# Sheet5.net
KiCad netlist of a schematic drawn in Altium Designer
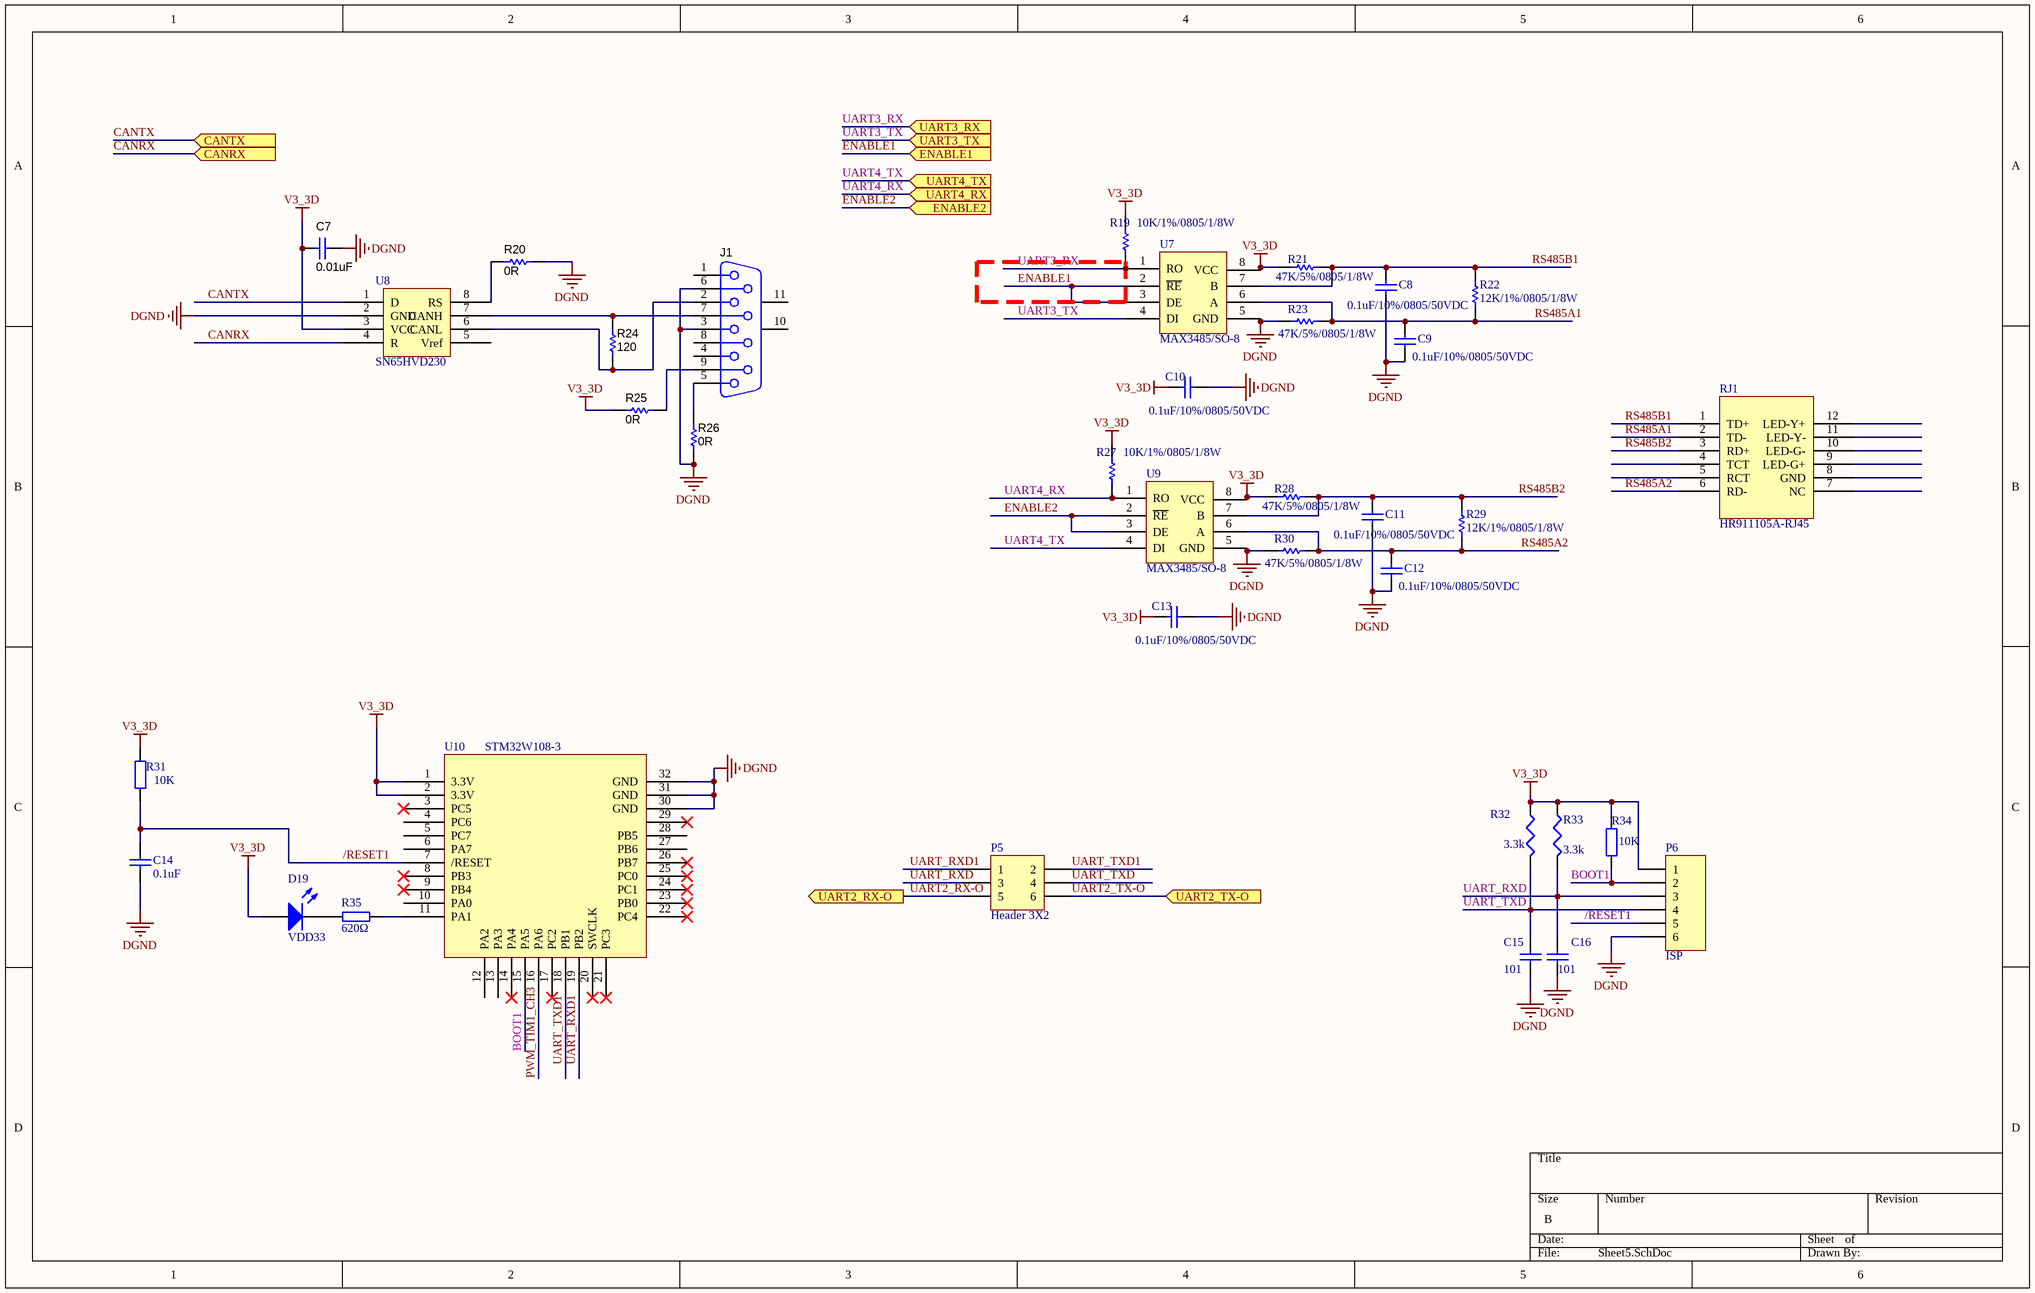
[diagram p0: Sheet5.SchDoc]

(export (version "E")
  (design (tool "Eeschema 10.0.6"))
  (components
    (comp (ref "C7")
      (value "~")
      (footprint "0805_cap")
      (description "CAP, CERM, 0.01uF, 16V, +/-10%, X7R, 0402")
      (fields
        (field (name "PARTNUMBER") "C1005X7R1C103K")
        (field (name "VALUEDISPLAYED") "0.01uF")
        (field (name "MANUFACTURER") "TDK")
        (field (name "PUBLISHER") "Texas Instruments")
      )
      (libsource (lib "Capacitor_Ceramic") (part "C1005X7R1C103K"))
    )
    (comp (ref "C8")
      (value "0.1uF/10%/0805/50VDC")
      (footprint "C-0805")
      (libsource (lib "浙江关西电机数据库") (part "CAP_Non-polarity"))
    )
    (comp (ref "C9")
      (value "0.1uF/10%/0805/50VDC")
      (footprint "C-0805")
      (libsource (lib "浙江关西电机数据库") (part "CAP_Non-polarity"))
    )
    (comp (ref "C10")
      (value "0.1uF/10%/0805/50VDC")
      (footprint "C-0805")
      (libsource (lib "浙江关西电机数据库") (part "CAP_Non-polarity"))
    )
    (comp (ref "C11")
      (value "0.1uF/10%/0805/50VDC")
      (footprint "C-0805")
      (libsource (lib "浙江关西电机数据库") (part "CAP_Non-polarity"))
    )
    (comp (ref "C12")
      (value "0.1uF/10%/0805/50VDC")
      (footprint "C-0805")
      (libsource (lib "浙江关西电机数据库") (part "CAP_Non-polarity"))
    )
    (comp (ref "C13")
      (value "0.1uF/10%/0805/50VDC")
      (footprint "C-0805")
      (libsource (lib "浙江关西电机数据库") (part "CAP_Non-polarity"))
    )
    (comp (ref "C14")
      (value "0.1uF")
      (footprint "C0805")
      (description "Capacitor")
      (fields (field (name "PUBLISHER") "Altium Limited"))
      (libsource (lib "Miscellaneous Devices") (part "Cap"))
    )
    (comp (ref "C15")
      (value "101")
      (footprint "C0805")
      (description "Capacitor")
      (fields (field (name "PUBLISHER") "Altium Limited"))
      (libsource (lib "Miscellaneous Devices") (part "Cap"))
    )
    (comp (ref "C16")
      (value "101")
      (footprint "C0805")
      (description "Capacitor")
      (fields (field (name "PUBLISHER") "Altium Limited"))
      (libsource (lib "Miscellaneous Devices") (part "Cap"))
    )
    (comp (ref "D19")
      (value "VDD33")
      (footprint "0805LED")
      (description "Typical BLUE SiC LED")
      (fields (field (name "PUBLISHER") "Altium Limited"))
      (libsource (lib "Miscellaneous Devices") (part "LED3"))
    )
    (comp (ref "J1")
      (value "~")
      (footprint "CONN_1734348-1")
      (description "Conn D-SUB RCPT R/A 9POS GOLD/FL, TH")
      (fields
        (field (name "PARTNUMBER") "1734348-1")
        (field (name "MANUFACTURER") "TE Connectivity")
        (field (name "SYMBOLCREATOR") "a0412235")
        (field (name "PUBLISHER") "Texas Instruments")
      )
      (libsource (lib "Connectors") (part "1734348-1"))
    )
    (comp (ref "P5")
      (value "Header 3X2")
      (footprint "HDR2X3")
      (description "Header, 3-Pin, Dual row")
      (fields (field (name "PUBLISHER") "Altium Limited"))
      (libsource (lib "Miscellaneous Connectors") (part "Header 3X2"))
    )
    (comp (ref "P6")
      (value "ISP")
      (footprint "SIP-6B")
      (description "Header, 6-Pin")
      (fields (field (name "PUBLISHER") "Altium Limited"))
      (libsource (lib "Miscellaneous Connectors") (part "Header 6"))
    )
    (comp (ref "R19")
      (value "10K/1%/0805/1/8W")
      (footprint "R-0805")
      (fields (field (name "PART NUMBER") "ASR-0028BA"))
      (libsource (lib "浙江关西电机数据库") (part "RES_1"))
    )
    (comp (ref "R20")
      (value "0R")
      (footprint "0805_HV")
      (description "RES, 0 ohm, 1%, 0.125W, 0805")
      (fields
        (field (name "PARTNUMBER") "CRCW080560R4FKEA")
        (field (name "MANUFACTURER") "Vishay-Dale")
        (field (name "PUBLISHER") "Texas Instruments")
      )
      (libsource (lib "Resistor_0805") (part "CRCW080560R4FKEA"))
    )
    (comp (ref "R21")
      (value "47K/5%/0805/1/8W")
      (footprint "R-0805")
      (fields (field (name "PART NUMBER") "ASR-0134BA"))
      (libsource (lib "浙江关西电机数据库") (part "RES_1"))
    )
    (comp (ref "R22")
      (value "12K/1%/0805/1/8W")
      (footprint "R-0805")
      (libsource (lib "浙江关西电机数据库") (part "RES_1"))
    )
    (comp (ref "R23")
      (value "47K/5%/0805/1/8W")
      (footprint "R-0805")
      (fields (field (name "PART NUMBER") "ASR-0134BA"))
      (libsource (lib "浙江关西电机数据库") (part "RES_1"))
    )
    (comp (ref "R24")
      (value "120")
      (footprint "0805_HV")
      (description "RES, 120ohm, 1%, 0.125W, 0805")
      (fields
        (field (name "PARTNUMBER") "CRCW080560R4FKEA")
        (field (name "MANUFACTURER") "Vishay-Dale")
        (field (name "PUBLISHER") "Texas Instruments")
      )
      (libsource (lib "Resistor_0805") (part "CRCW080560R4FKEA"))
    )
    (comp (ref "R25")
      (value "0R")
      (footprint "0805_HV")
      (description "RES, 0 ohm, 1%, 0.125W, 0805")
      (fields
        (field (name "PARTNUMBER") "CRCW080560R4FKEA")
        (field (name "MANUFACTURER") "Vishay-Dale")
        (field (name "PUBLISHER") "Texas Instruments")
      )
      (libsource (lib "Resistor_0805") (part "CRCW080560R4FKEA"))
    )
    (comp (ref "R26")
      (value "0R")
      (footprint "0805_HV")
      (description "RES, 0 ohm, 1%, 0.125W, 0805")
      (fields
        (field (name "PARTNUMBER") "CRCW080560R4FKEA")
        (field (name "MANUFACTURER") "Vishay-Dale")
        (field (name "PUBLISHER") "Texas Instruments")
      )
      (libsource (lib "Resistor_0805") (part "CRCW080560R4FKEA"))
    )
    (comp (ref "R27")
      (value "10K/1%/0805/1/8W")
      (footprint "R-0805")
      (fields (field (name "PART NUMBER") "ASR-0028BA"))
      (libsource (lib "浙江关西电机数据库") (part "RES_1"))
    )
    (comp (ref "R28")
      (value "47K/5%/0805/1/8W")
      (footprint "R-0805")
      (fields (field (name "PART NUMBER") "ASR-0134BA"))
      (libsource (lib "浙江关西电机数据库") (part "RES_1"))
    )
    (comp (ref "R29")
      (value "12K/1%/0805/1/8W")
      (footprint "R-0805")
      (libsource (lib "浙江关西电机数据库") (part "RES_1"))
    )
    (comp (ref "R30")
      (value "47K/5%/0805/1/8W")
      (footprint "R-0805")
      (fields (field (name "PART NUMBER") "ASR-0134BA"))
      (libsource (lib "浙江关西电机数据库") (part "RES_1"))
    )
    (comp (ref "R31")
      (value "10K")
      (footprint "0805")
      (description "Resistor")
      (fields (field (name "Comment") "Res2") (field (name "PUBLISHER") "Altium Limited"))
      (libsource (lib "Miscellaneous Devices") (part "Res2"))
    )
    (comp (ref "R32")
      (value "3.3k")
      (footprint "R0805")
      (description "Resistor")
      (fields (field (name "PUBLISHER") "Altium Limited"))
      (libsource (lib "Miscellaneous Devices") (part "Res3"))
    )
    (comp (ref "R33")
      (value "3.3k")
      (footprint "R0805")
      (description "Resistor")
      (fields (field (name "PUBLISHER") "Altium Limited"))
      (libsource (lib "Miscellaneous Devices") (part "Res3"))
    )
    (comp (ref "R34")
      (value "10K")
      (footprint "R0805")
      (description "Resistor")
      (fields (field (name "Comment") "Res2") (field (name "PUBLISHER") "Altium Limited"))
      (libsource (lib "Miscellaneous Devices") (part "Res2"))
    )
    (comp (ref "R35")
      (value "620Ω")
      (footprint "R0805")
      (description "R")
      (libsource (lib "Haze") (part "RES"))
    )
    (comp (ref "RJ1")
      (value "HR911105A-RJ45")
      (footprint "HR911105A")
      (libsource (lib "moonlight") (part "HR911105A-RJ45"))
    )
    (comp (ref "U7")
      (value "MAX3485/SO-8")
      (footprint "SO-G8")
      (libsource (lib "SCHLIBRARIES") (part "MAX485"))
    )
    (comp (ref "U8")
      (value "SN65HVD230")
      (footprint "SO-G8")
      (libsource (lib "SCHLIBRARIES") (part "SN65HVD230"))
    )
    (comp (ref "U9")
      (value "MAX3485/SO-8")
      (footprint "SO-G8")
      (libsource (lib "SCHLIBRARIES") (part "MAX485"))
    )
    (comp (ref "U10")
      (value "STM32W108-3")
      (footprint "STM32W108-3")
      (libsource (lib "STM32W108-3") (part "STM32W108-3"))
    )
  )
  (nets
    (net (code "1") (name "/BOOT1") (class "Default")
      (node (ref "P6") (pin "2") (pinfunction "2_2") (pintype "passive"))
      (node (ref "R34") (pin "1") (pinfunction "1_1") (pintype "passive"))
      (node (ref "U10") (pin "15") (pinfunction "PA5_15") (pintype "passive"))
    )
    (net (code "2") (name "/CANRX") (class "Default")
      (node (ref "U8") (pin "4") (pinfunction "R_4") (pintype "passive"))
    )
    (net (code "3") (name "/CANTX") (class "Default")
      (node (ref "U8") (pin "1") (pinfunction "D_1") (pintype "passive"))
    )
    (net (code "4") (name "/ENABLE1") (class "Default")
      (node (ref "U7") (pin "2") (pinfunction "~{RE}_2") (pintype "passive"))
      (node (ref "U7") (pin "3") (pinfunction "DE_3") (pintype "passive"))
    )
    (net (code "5") (name "/ENABLE2") (class "Default")
      (node (ref "U9") (pin "2") (pinfunction "~{RE}_2") (pintype "passive"))
      (node (ref "U9") (pin "3") (pinfunction "DE_3") (pintype "passive"))
    )
    (net (code "6") (name "/PWM_TIM1_CH3") (class "Default")
      (node (ref "U10") (pin "16") (pinfunction "PA6_16") (pintype "passive"))
    )
    (net (code "7") (name "/RS485A1") (class "Default")
      (node (ref "C9") (pin "2") (pinfunction "2_2") (pintype "passive"))
      (node (ref "R22") (pin "1") (pinfunction "1_1") (pintype "passive"))
      (node (ref "R23") (pin "1") (pinfunction "1_1") (pintype "passive"))
      (node (ref "RJ1") (pin "2") (pinfunction "TD-_2") (pintype "passive"))
      (node (ref "U7") (pin "6") (pinfunction "A_6") (pintype "passive"))
    )
    (net (code "8") (name "/RS485A2") (class "Default")
      (node (ref "C12") (pin "2") (pinfunction "2_2") (pintype "passive"))
      (node (ref "R29") (pin "1") (pinfunction "1_1") (pintype "passive"))
      (node (ref "R30") (pin "1") (pinfunction "1_1") (pintype "passive"))
      (node (ref "RJ1") (pin "6") (pinfunction "RD-_6") (pintype "passive"))
      (node (ref "U9") (pin "6") (pinfunction "A_6") (pintype "passive"))
    )
    (net (code "9") (name "/RS485B1") (class "Default")
      (node (ref "C8") (pin "2") (pinfunction "2_2") (pintype "passive"))
      (node (ref "R21") (pin "1") (pinfunction "1_1") (pintype "passive"))
      (node (ref "R22") (pin "2") (pinfunction "2_2") (pintype "passive"))
      (node (ref "RJ1") (pin "1") (pinfunction "TD+_1") (pintype "passive"))
      (node (ref "U7") (pin "7") (pinfunction "B_7") (pintype "passive"))
    )
    (net (code "10") (name "/RS485B2") (class "Default")
      (node (ref "C11") (pin "2") (pinfunction "2_2") (pintype "passive"))
      (node (ref "R28") (pin "1") (pinfunction "1_1") (pintype "passive"))
      (node (ref "R29") (pin "2") (pinfunction "2_2") (pintype "passive"))
      (node (ref "RJ1") (pin "3") (pinfunction "RD+_3") (pintype "passive"))
      (node (ref "U9") (pin "7") (pinfunction "B_7") (pintype "passive"))
    )
    (net (code "11") (name "/UART2_RX-O") (class "Default")
      (node (ref "P5") (pin "5") (pinfunction "5_5") (pintype "passive"))
    )
    (net (code "12") (name "/UART2_TX-O") (class "Default")
      (node (ref "P5") (pin "6") (pinfunction "6_6") (pintype "passive"))
    )
    (net (code "13") (name "/UART3_RX") (class "Default")
      (node (ref "R19") (pin "1") (pinfunction "1_1") (pintype "passive"))
      (node (ref "U7") (pin "1") (pinfunction "RO_1") (pintype "passive"))
    )
    (net (code "14") (name "/UART3_TX") (class "Default")
      (node (ref "U7") (pin "4") (pinfunction "DI_4") (pintype "passive"))
    )
    (net (code "15") (name "/UART4_RX") (class "Default")
      (node (ref "R27") (pin "1") (pinfunction "1_1") (pintype "passive"))
      (node (ref "U9") (pin "1") (pinfunction "RO_1") (pintype "passive"))
    )
    (net (code "16") (name "/UART4_TX") (class "Default")
      (node (ref "U9") (pin "4") (pinfunction "DI_4") (pintype "passive"))
    )
    (net (code "17") (name "/UART_RXD") (class "Default")
      (node (ref "C16") (pin "2") (pinfunction "2_2") (pintype "passive"))
      (node (ref "P5") (pin "3") (pinfunction "3_3") (pintype "passive"))
      (node (ref "P6") (pin "3") (pinfunction "3_3") (pintype "passive"))
      (node (ref "R33") (pin "2") (pinfunction "2_2") (pintype "passive"))
    )
    (net (code "18") (name "/UART_RXD1") (class "Default")
      (node (ref "P5") (pin "1") (pinfunction "1_1") (pintype "passive"))
      (node (ref "U10") (pin "19") (pinfunction "PB2_19") (pintype "passive"))
    )
    (net (code "19") (name "/UART_TXD") (class "Default")
      (node (ref "C15") (pin "2") (pinfunction "2_2") (pintype "passive"))
      (node (ref "P5") (pin "4") (pinfunction "4_4") (pintype "passive"))
      (node (ref "P6") (pin "4") (pinfunction "4_4") (pintype "passive"))
      (node (ref "R32") (pin "2") (pinfunction "2_2") (pintype "passive"))
    )
    (net (code "20") (name "/UART_TXD1") (class "Default")
      (node (ref "P5") (pin "2") (pinfunction "2_2") (pintype "passive"))
      (node (ref "U10") (pin "18") (pinfunction "PB1_18") (pintype "passive"))
    )
    (net (code "21") (name "/{slash}RESET1") (class "Default")
      (node (ref "C14") (pin "2") (pinfunction "2_2") (pintype "passive"))
      (node (ref "P6") (pin "5") (pinfunction "5_5") (pintype "passive"))
      (node (ref "R31") (pin "1") (pinfunction "1_1") (pintype "passive"))
      (node (ref "U10") (pin "7") (pinfunction "/RESET_7") (pintype "passive"))
    )
    (net (code "22") (name "DGND") (class "Default")
      (node (ref "C10") (pin "2") (pinfunction "2_2") (pintype "passive"))
      (node (ref "C11") (pin "1") (pinfunction "1_1") (pintype "passive"))
      (node (ref "C12") (pin "1") (pinfunction "1_1") (pintype "passive"))
      (node (ref "C13") (pin "2") (pinfunction "2_2") (pintype "passive"))
      (node (ref "C14") (pin "1") (pinfunction "1_1") (pintype "passive"))
      (node (ref "C15") (pin "1") (pinfunction "1_1") (pintype "passive"))
      (node (ref "C16") (pin "1") (pinfunction "1_1") (pintype "passive"))
      (node (ref "C7") (pin "2") (pinfunction "2_2") (pintype "passive"))
      (node (ref "C8") (pin "1") (pinfunction "1_1") (pintype "passive"))
      (node (ref "C9") (pin "1") (pinfunction "1_1") (pintype "passive"))
      (node (ref "J1") (pin "3") (pinfunction "3_3") (pintype "passive"))
      (node (ref "J1") (pin "6") (pinfunction "6_6") (pintype "passive"))
      (node (ref "P6") (pin "6") (pinfunction "6_6") (pintype "passive"))
      (node (ref "R20") (pin "2") (pinfunction "2_2") (pintype "passive"))
      (node (ref "R23") (pin "2") (pinfunction "2_2") (pintype "passive"))
      (node (ref "R26") (pin "1") (pinfunction "1_1") (pintype "passive"))
      (node (ref "R30") (pin "2") (pinfunction "2_2") (pintype "passive"))
      (node (ref "U10") (pin "30") (pinfunction "GND_30") (pintype "passive"))
      (node (ref "U10") (pin "31") (pinfunction "GND_31") (pintype "passive"))
      (node (ref "U10") (pin "32") (pinfunction "GND_32") (pintype "passive"))
      (node (ref "U7") (pin "5") (pinfunction "GND_5") (pintype "passive"))
      (node (ref "U8") (pin "2") (pinfunction "GND_2") (pintype "passive"))
      (node (ref "U9") (pin "5") (pinfunction "GND_5") (pintype "passive"))
    )
    (net (code "23") (name "Net-(D19-K)") (class "Default")
      (node (ref "D19") (pin "2") (pinfunction "K_2") (pintype "passive"))
      (node (ref "R35") (pin "2") (pinfunction "2_2") (pintype "passive"))
    )
    (net (code "24") (name "Net-(J1-Pad5)") (class "Default")
      (node (ref "J1") (pin "5") (pinfunction "5_5") (pintype "passive"))
      (node (ref "R26") (pin "2") (pinfunction "2_2") (pintype "passive"))
    )
    (net (code "25") (name "Net-(J1-Pad9)") (class "Default")
      (node (ref "J1") (pin "9") (pinfunction "9_9") (pintype "passive"))
      (node (ref "R25") (pin "1") (pinfunction "1_1") (pintype "passive"))
    )
    (net (code "26") (name "Net-(U8-CANH)") (class "Default")
      (node (ref "J1") (pin "7") (pinfunction "7_7") (pintype "passive"))
      (node (ref "R24") (pin "1") (pinfunction "1_1") (pintype "passive"))
      (node (ref "U8") (pin "7") (pinfunction "CANH_7") (pintype "passive"))
    )
    (net (code "27") (name "Net-(U8-CANL)") (class "Default")
      (node (ref "J1") (pin "2") (pinfunction "2_2") (pintype "passive"))
      (node (ref "R24") (pin "2") (pinfunction "2_2") (pintype "passive"))
      (node (ref "U8") (pin "6") (pinfunction "CANL_6") (pintype "passive"))
    )
    (net (code "28") (name "Net-(U8-RS)") (class "Default")
      (node (ref "R20") (pin "1") (pinfunction "1_1") (pintype "passive"))
      (node (ref "U8") (pin "8") (pinfunction "RS_8") (pintype "passive"))
    )
    (net (code "29") (name "Net-(U10-PA1)") (class "Default")
      (node (ref "R35") (pin "1") (pinfunction "1_1") (pintype "passive"))
      (node (ref "U10") (pin "11") (pinfunction "PA1_11") (pintype "passive"))
    )
    (net (code "30") (name "V3_3D") (class "Default")
      (node (ref "C10") (pin "1") (pinfunction "1_1") (pintype "passive"))
      (node (ref "C13") (pin "1") (pinfunction "1_1") (pintype "passive"))
      (node (ref "C7") (pin "1") (pinfunction "1_1") (pintype "passive"))
      (node (ref "D19") (pin "1") (pinfunction "A_1") (pintype "passive"))
      (node (ref "P6") (pin "1") (pinfunction "1_1") (pintype "passive"))
      (node (ref "R19") (pin "2") (pinfunction "2_2") (pintype "passive"))
      (node (ref "R21") (pin "2") (pinfunction "2_2") (pintype "passive"))
      (node (ref "R25") (pin "2") (pinfunction "2_2") (pintype "passive"))
      (node (ref "R27") (pin "2") (pinfunction "2_2") (pintype "passive"))
      (node (ref "R28") (pin "2") (pinfunction "2_2") (pintype "passive"))
      (node (ref "R31") (pin "2") (pinfunction "2_2") (pintype "passive"))
      (node (ref "R32") (pin "1") (pinfunction "1_1") (pintype "passive"))
      (node (ref "R33") (pin "1") (pinfunction "1_1") (pintype "passive"))
      (node (ref "R34") (pin "2") (pinfunction "2_2") (pintype "passive"))
      (node (ref "U10") (pin "1") (pinfunction "3.3V_1") (pintype "passive"))
      (node (ref "U10") (pin "2") (pinfunction "3.3V_2") (pintype "passive"))
      (node (ref "U7") (pin "8") (pinfunction "VCC_8") (pintype "passive"))
      (node (ref "U8") (pin "3") (pinfunction "VCC_3") (pintype "passive"))
      (node (ref "U9") (pin "8") (pinfunction "VCC_8") (pintype "passive"))
    )
    (net (code "31") (name "unconnected-(J1-MH1-Pad10)") (class "Default")
      (node (ref "J1") (pin "10") (pinfunction "MH1_10") (pintype "passive"))
    )
    (net (code "32") (name "unconnected-(J1-MH2-Pad11)") (class "Default")
      (node (ref "J1") (pin "11") (pinfunction "MH2_11") (pintype "passive"))
    )
    (net (code "33") (name "unconnected-(J1-Pad1)") (class "Default")
      (node (ref "J1") (pin "1") (pinfunction "1_1") (pintype "passive"))
    )
    (net (code "34") (name "unconnected-(J1-Pad4)") (class "Default")
      (node (ref "J1") (pin "4") (pinfunction "4_4") (pintype "passive"))
    )
    (net (code "35") (name "unconnected-(J1-Pad8)") (class "Default")
      (node (ref "J1") (pin "8") (pinfunction "8_8") (pintype "passive"))
    )
    (net (code "36") (name "unconnected-(RJ1-GND-Pad8)") (class "Default")
      (node (ref "RJ1") (pin "8") (pinfunction "GND_8") (pintype "passive"))
    )
    (net (code "37") (name "unconnected-(RJ1-LED-G+-Pad9)") (class "Default")
      (node (ref "RJ1") (pin "9") (pinfunction "LED-G+_9") (pintype "passive"))
    )
    (net (code "38") (name "unconnected-(RJ1-LED-G--Pad10)") (class "Default")
      (node (ref "RJ1") (pin "10") (pinfunction "LED-G-_10") (pintype "passive"))
    )
    (net (code "39") (name "unconnected-(RJ1-LED-Y+-Pad12)") (class "Default")
      (node (ref "RJ1") (pin "12") (pinfunction "LED-Y+_12") (pintype "passive"))
    )
    (net (code "40") (name "unconnected-(RJ1-LED-Y--Pad11)") (class "Default")
      (node (ref "RJ1") (pin "11") (pinfunction "LED-Y-_11") (pintype "passive"))
    )
    (net (code "41") (name "unconnected-(RJ1-NC-Pad7)") (class "Default")
      (node (ref "RJ1") (pin "7") (pinfunction "NC_7") (pintype "passive"))
    )
    (net (code "42") (name "unconnected-(RJ1-RCT-Pad5)") (class "Default")
      (node (ref "RJ1") (pin "5") (pinfunction "RCT_5") (pintype "passive"))
    )
    (net (code "43") (name "unconnected-(RJ1-TCT-Pad4)") (class "Default")
      (node (ref "RJ1") (pin "4") (pinfunction "TCT_4") (pintype "passive"))
    )
    (net (code "44") (name "unconnected-(U8-Vref-Pad5)") (class "Default")
      (node (ref "U8") (pin "5") (pinfunction "Vref_5") (pintype "passive"))
    )
    (net (code "45") (name "unconnected-(U10-PA0-Pad10)") (class "Default")
      (node (ref "U10") (pin "10") (pinfunction "PA0_10") (pintype "passive"))
    )
    (net (code "46") (name "unconnected-(U10-PA2-Pad12)") (class "Default")
      (node (ref "U10") (pin "12") (pinfunction "PA2_12") (pintype "passive"))
    )
    (net (code "47") (name "unconnected-(U10-PA3-Pad13)") (class "Default")
      (node (ref "U10") (pin "13") (pinfunction "PA3_13") (pintype "passive"))
    )
    (net (code "48") (name "unconnected-(U10-PA4-Pad14)") (class "Default")
      (node (ref "U10") (pin "14") (pinfunction "PA4_14") (pintype "passive+no_connect"))
    )
    (net (code "49") (name "unconnected-(U10-PA7-Pad6)") (class "Default")
      (node (ref "U10") (pin "6") (pinfunction "PA7_6") (pintype "passive"))
    )
    (net (code "50") (name "unconnected-(U10-PB0-Pad23)") (class "Default")
      (node (ref "U10") (pin "23") (pinfunction "PB0_23") (pintype "passive+no_connect"))
    )
    (net (code "51") (name "unconnected-(U10-PB3-Pad8)") (class "Default")
      (node (ref "U10") (pin "8") (pinfunction "PB3_8") (pintype "passive+no_connect"))
    )
    (net (code "52") (name "unconnected-(U10-PB4-Pad9)") (class "Default")
      (node (ref "U10") (pin "9") (pinfunction "PB4_9") (pintype "passive+no_connect"))
    )
    (net (code "53") (name "unconnected-(U10-PB5-Pad28)") (class "Default")
      (node (ref "U10") (pin "28") (pinfunction "PB5_28") (pintype "passive"))
    )
    (net (code "54") (name "unconnected-(U10-PB6-Pad27)") (class "Default")
      (node (ref "U10") (pin "27") (pinfunction "PB6_27") (pintype "passive"))
    )
    (net (code "55") (name "unconnected-(U10-PB7-Pad26)") (class "Default")
      (node (ref "U10") (pin "26") (pinfunction "PB7_26") (pintype "passive+no_connect"))
    )
    (net (code "56") (name "unconnected-(U10-PC0-Pad25)") (class "Default")
      (node (ref "U10") (pin "25") (pinfunction "PC0_25") (pintype "passive+no_connect"))
    )
    (net (code "57") (name "unconnected-(U10-PC1-Pad24)") (class "Default")
      (node (ref "U10") (pin "24") (pinfunction "PC1_24") (pintype "passive+no_connect"))
    )
    (net (code "58") (name "unconnected-(U10-PC2-Pad17)") (class "Default")
      (node (ref "U10") (pin "17") (pinfunction "PC2_17") (pintype "passive+no_connect"))
    )
    (net (code "59") (name "unconnected-(U10-PC3-Pad21)") (class "Default")
      (node (ref "U10") (pin "21") (pinfunction "PC3_21") (pintype "passive+no_connect"))
    )
    (net (code "60") (name "unconnected-(U10-PC4-Pad22)") (class "Default")
      (node (ref "U10") (pin "22") (pinfunction "PC4_22") (pintype "passive+no_connect"))
    )
    (net (code "61") (name "unconnected-(U10-PC5-Pad3)") (class "Default")
      (node (ref "U10") (pin "3") (pinfunction "PC5_3") (pintype "passive+no_connect"))
    )
    (net (code "62") (name "unconnected-(U10-PC6-Pad4)") (class "Default")
      (node (ref "U10") (pin "4") (pinfunction "PC6_4") (pintype "passive"))
    )
    (net (code "63") (name "unconnected-(U10-PC7-Pad5)") (class "Default")
      (node (ref "U10") (pin "5") (pinfunction "PC7_5") (pintype "passive"))
    )
    (net (code "64") (name "unconnected-(U10-Pad29)") (class "Default")
      (node (ref "U10") (pin "29") (pintype "passive+no_connect"))
    )
    (net (code "65") (name "unconnected-(U10-SWCLK-Pad20)") (class "Default")
      (node (ref "U10") (pin "20") (pinfunction "SWCLK_20") (pintype "passive+no_connect"))
    )
  )
)
